# power-supply.net
KiCad netlist of a schematic drawn in EAGLE
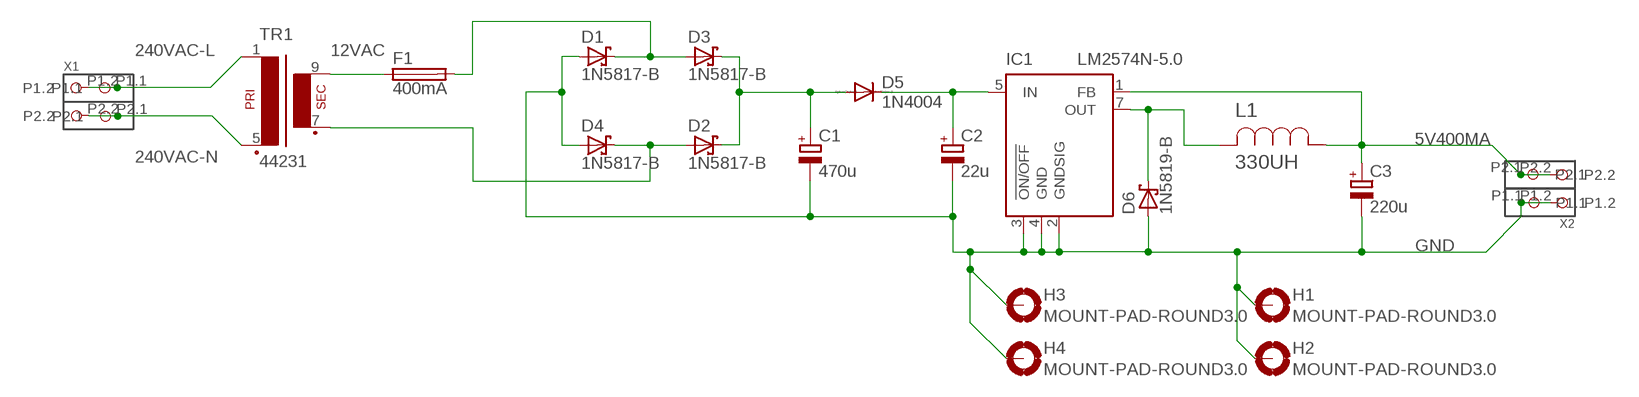
[diagram p0: schematic, sheet 1]

(export (version "E")
  (design (tool "Eeschema 10.0.6"))
  (components
    (comp (ref "C1")
      (value "470u")
      (footprint "eagle-import:E3,5-8")
      (libsource (lib "eagle-import") (part "CPOL-EUE3.5-8"))
    )
    (comp (ref "C2")
      (value "22u")
      (footprint "eagle-import:E2-4")
      (libsource (lib "eagle-import") (part "CPOL-EUE2-4"))
    )
    (comp (ref "C3")
      (value "220u")
      (footprint "eagle-import:E2-5")
      (libsource (lib "eagle-import") (part "CPOL-EUE2-5"))
    )
    (comp (ref "D1")
      (value "1N5817-B")
      (footprint "eagle-import:DO41-7.6")
      (libsource (lib "eagle-import") (part "1N5817-B"))
    )
    (comp (ref "D2")
      (value "1N5817-B")
      (footprint "eagle-import:DO41-7.6")
      (libsource (lib "eagle-import") (part "1N5817-B"))
    )
    (comp (ref "D3")
      (value "1N5817-B")
      (footprint "eagle-import:DO41-7.6")
      (libsource (lib "eagle-import") (part "1N5817-B"))
    )
    (comp (ref "D4")
      (value "1N5817-B")
      (footprint "eagle-import:DO41-7.6")
      (libsource (lib "eagle-import") (part "1N5817-B"))
    )
    (comp (ref "D5")
      (value "1N4004")
      (footprint "eagle-import:DO41-10")
      (libsource (lib "eagle-import") (part "1N4004"))
    )
    (comp (ref "D6")
      (value "1N5819-B")
      (footprint "eagle-import:DO41-7.6")
      (libsource (lib "eagle-import") (part "1N5819-B"))
    )
    (comp (ref "F1")
      (value "400mA")
      (footprint "eagle-import:SH22,5")
      (fields (field (name "MF") "SCHURTER") (field (name "MPN") "0031.8201"))
      (libsource (lib "eagle-import") (part "SH22,5"))
    )
    (comp (ref "H1")
      (value "MOUNT-PAD-ROUND3.0")
      (footprint "eagle-import:3,0-PAD")
      (libsource (lib "eagle-import") (part "MOUNT-PAD-ROUND3.0"))
    )
    (comp (ref "H2")
      (value "MOUNT-PAD-ROUND3.0")
      (footprint "eagle-import:3,0-PAD")
      (libsource (lib "eagle-import") (part "MOUNT-PAD-ROUND3.0"))
    )
    (comp (ref "H3")
      (value "MOUNT-PAD-ROUND3.0")
      (footprint "eagle-import:3,0-PAD")
      (libsource (lib "eagle-import") (part "MOUNT-PAD-ROUND3.0"))
    )
    (comp (ref "H4")
      (value "MOUNT-PAD-ROUND3.0")
      (footprint "eagle-import:3,0-PAD")
      (libsource (lib "eagle-import") (part "MOUNT-PAD-ROUND3.0"))
    )
    (comp (ref "IC1")
      (value "LM2574N-5.0")
      (footprint "eagle-import:DIL08")
      (libsource (lib "eagle-import") (part "LM2574?-N5.0"))
    )
    (comp (ref "L1")
      (value "330UH")
      (footprint "eagle-import:IND_ELC11D")
      (fields (field (name "MPN") "ELC11D331F"))
      (libsource (lib "eagle-import") (part "ELC-11D11D331F"))
    )
    (comp (ref "TR1")
      (value "44231")
      (footprint "eagle-import:EI42-1")
      (libsource (lib "eagle-import") (part "EI42-1"))
    )
    (comp (ref "X1")
      (value "2604-1102")
      (footprint "eagle-import:P-2604-1102")
      (libsource (lib "eagle-import") (part "2604-1102"))
    )
    (comp (ref "X2")
      (value "2604-1102")
      (footprint "eagle-import:P-2604-1102")
      (libsource (lib "eagle-import") (part "2604-1102"))
    )
  )
  (nets
    (net (code "1") (name "/5V400MA") (class "Default")
      (node (ref "C3") (pin "+") (pinfunction "+_+") (pintype "passive"))
      (node (ref "IC1") (pin "1") (pinfunction "FB_1") (pintype "input"))
      (node (ref "L1") (pin "1") (pinfunction "1_1") (pintype "passive"))
      (node (ref "X2") (pin "P2.1") (pinfunction "P2.1_P2.1") (pintype "bidirectional"))
      (node (ref "X2") (pin "P2.2") (pinfunction "P2.2_P2.2") (pintype "bidirectional"))
    )
    (net (code "2") (name "/12VAC") (class "Default")
      (node (ref "F1") (pin "1") (pinfunction "1_1") (pintype "passive"))
      (node (ref "TR1") (pin "9") (pinfunction "S4_9") (pintype "passive"))
    )
    (net (code "3") (name "/240VAC-L") (class "Default")
      (node (ref "TR1") (pin "1") (pinfunction "P1_1") (pintype "passive"))
      (node (ref "X1") (pin "P1.1") (pinfunction "P1.1_P1.1") (pintype "bidirectional"))
      (node (ref "X1") (pin "P1.2") (pinfunction "P1.2_P1.2") (pintype "bidirectional"))
    )
    (net (code "4") (name "/240VAC-N") (class "Default")
      (node (ref "TR1") (pin "5") (pinfunction "P2_5") (pintype "passive"))
      (node (ref "X1") (pin "P2.1") (pinfunction "P2.1_P2.1") (pintype "bidirectional"))
      (node (ref "X1") (pin "P2.2") (pinfunction "P2.2_P2.2") (pintype "bidirectional"))
    )
    (net (code "5") (name "/GND") (class "Default")
      (node (ref "C1") (pin "-") (pinfunction "-_-") (pintype "passive"))
      (node (ref "C2") (pin "-") (pinfunction "-_-") (pintype "passive"))
      (node (ref "C3") (pin "-") (pinfunction "-_-") (pintype "passive"))
      (node (ref "D1") (pin "A") (pinfunction "A_A") (pintype "passive"))
      (node (ref "D4") (pin "A") (pinfunction "A_A") (pintype "passive"))
      (node (ref "D6") (pin "A") (pinfunction "A_A") (pintype "passive"))
      (node (ref "H1") (pin "B3,0") (pinfunction "MOUNT_B3,0") (pintype "passive"))
      (node (ref "H2") (pin "B3,0") (pinfunction "MOUNT_B3,0") (pintype "passive"))
      (node (ref "H3") (pin "B3,0") (pinfunction "MOUNT_B3,0") (pintype "passive"))
      (node (ref "H4") (pin "B3,0") (pinfunction "MOUNT_B3,0") (pintype "passive"))
      (node (ref "IC1") (pin "2") (pinfunction "GNDSIG_2") (pintype "input"))
      (node (ref "IC1") (pin "3") (pinfunction "~{ON/OFF}_3") (pintype "input"))
      (node (ref "IC1") (pin "4") (pinfunction "GND_4") (pintype "power_in"))
      (node (ref "X2") (pin "P1.1") (pinfunction "P1.1_P1.1") (pintype "bidirectional"))
      (node (ref "X2") (pin "P1.2") (pinfunction "P1.2_P1.2") (pintype "bidirectional"))
    )
    (net (code "6") (name "Net-(C1-Pad+)") (class "Default")
      (node (ref "C1") (pin "+") (pinfunction "+_+") (pintype "passive"))
      (node (ref "D2") (pin "C") (pinfunction "C_C") (pintype "passive"))
      (node (ref "D3") (pin "C") (pinfunction "C_C") (pintype "passive"))
      (node (ref "D5") (pin "A") (pinfunction "A_A") (pintype "passive"))
    )
    (net (code "7") (name "Net-(D1-PadC)") (class "Default")
      (node (ref "D1") (pin "C") (pinfunction "C_C") (pintype "passive"))
      (node (ref "D3") (pin "A") (pinfunction "A_A") (pintype "passive"))
      (node (ref "F1") (pin "2") (pinfunction "2_2") (pintype "passive"))
    )
    (net (code "8") (name "Net-(IC1-IN)") (class "Default")
      (node (ref "C2") (pin "+") (pinfunction "+_+") (pintype "passive"))
      (node (ref "D5") (pin "C") (pinfunction "C_C") (pintype "passive"))
      (node (ref "IC1") (pin "5") (pinfunction "IN_5") (pintype "input"))
    )
    (net (code "9") (name "Net-(IC1-OUT)") (class "Default")
      (node (ref "D6") (pin "C") (pinfunction "C_C") (pintype "passive"))
      (node (ref "IC1") (pin "7") (pinfunction "OUT_7") (pintype "passive"))
      (node (ref "L1") (pin "2") (pinfunction "2_2") (pintype "passive"))
    )
    (net (code "10") (name "Net-(TR1-S3)") (class "Default")
      (node (ref "D2") (pin "A") (pinfunction "A_A") (pintype "passive"))
      (node (ref "D4") (pin "C") (pinfunction "C_C") (pintype "passive"))
      (node (ref "TR1") (pin "7") (pinfunction "S3_7") (pintype "passive"))
    )
  )
)
